# AMP_RF.net
KiCad netlist of a schematic drawn in Altium Designer
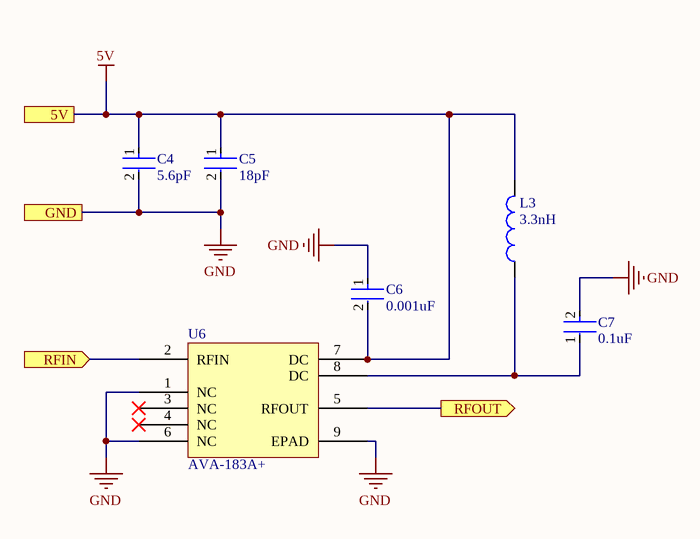
[diagram p0: AMP_RF.SchDoc]

(export (version "E")
  (design (tool "Eeschema 10.0.6"))
  (components
    (comp (ref "C4")
      (value "5.6pF")
      (footprint "FP-0402-L_1_0_1-W_0_5_0_1-MFG")
      (description "General Purpose Ceramic Capacitor, 0402, 5.6pF, 0.25pF, C0G, 30ppm/°C, 50V")
      (fields (field (name "VOLTAGE") "50V"))
      (libsource (lib "Altium Content Vault") (part "b4654b650e69147ec39a6b967a45e02"))
    )
    (comp (ref "C5")
      (value "18pF")
      (footprint "FP-0402-L_1_0_1-W_0_5_0_1-IPC_A")
      (description "General Purpose Ceramic Capacitor, 0402, 18pF, 1%, C0G, 30ppm/°C, 50V")
      (fields (field (name "TOLERANCE") "1%"))
      (libsource (lib "Altium Content Vault") (part "b4654b650e69147ec39a6b967a45e02"))
    )
    (comp (ref "C6")
      (value "0.001uF")
      (footprint "FP-C0402-BB-MFG")
      (description "C0402 1,000 pF C0G 5.00% 25 V")
      (fields (field (name "MANUFACTURER PART NUMBER") "C0402C102J3GACTU"))
      (libsource (lib "Altium Content Vault") (part "b4654b650e69147ec39a6b967a45e02"))
    )
    (comp (ref "C7")
      (value "0.1uF")
      (footprint "FP-GRM15-MFG")
      (description "CAP CER 0.1UF 16V X7R 0402")
      (fields (field (name "MANUFACTURER PART NUMBER") "GRM155R71C104KA88D") (field (name "TOLERANCE") "10%"))
      (libsource (lib "Altium Content Vault") (part "236180d848d6139a670b325ea6854c9"))
    )
    (comp (ref "L3")
      (value "3.3nH")
      (footprint "WE-KI_0805")
      (description "744760033A WE-KI SMT Wire Wound Ceramic Inductor")
      (libsource (lib "Altium Content Vault") (part "Inductor - 1"))
    )
    (comp (ref "U6")
      (value "AVA-183A+")
      (footprint "AVA-183A+ QFN")
      (description "Wideband, Microwave, Monolithic Amplifier, 50Ω, 5 to 18 GHz")
      (libsource (lib "FullyDigital") (part "AVA-183A+"))
    )
  )
  (nets
    (net (code "1") (name "/RFIN") (class "Default")
      (node (ref "U6") (pin "2") (pinfunction "RFIN_2") (pintype "passive"))
    )
    (net (code "2") (name "/RFOUT") (class "Default")
      (node (ref "U6") (pin "5") (pinfunction "RFOUT_5") (pintype "passive"))
    )
    (net (code "3") (name "5V") (class "Default")
      (node (ref "C4") (pin "1") (pinfunction "1_1") (pintype "passive"))
      (node (ref "C5") (pin "1") (pinfunction "1_1") (pintype "passive"))
      (node (ref "C6") (pin "2") (pinfunction "2_2") (pintype "passive"))
      (node (ref "L3") (pin "2") (pinfunction "2_2") (pintype "passive"))
      (node (ref "U6") (pin "7") (pinfunction "DC_7") (pintype "passive"))
    )
    (net (code "4") (name "GND") (class "Default")
      (node (ref "C4") (pin "2") (pinfunction "2_2") (pintype "passive"))
      (node (ref "C5") (pin "2") (pinfunction "2_2") (pintype "passive"))
      (node (ref "C6") (pin "1") (pinfunction "1_1") (pintype "passive"))
      (node (ref "C7") (pin "2") (pinfunction "2_2") (pintype "passive"))
      (node (ref "U6") (pin "1") (pinfunction "NC_1") (pintype "passive"))
      (node (ref "U6") (pin "6") (pinfunction "NC_6") (pintype "passive"))
      (node (ref "U6") (pin "9") (pinfunction "EPAD_9") (pintype "passive"))
    )
    (net (code "5") (name "Net-(C7-Pad1)") (class "Default")
      (node (ref "C7") (pin "1") (pinfunction "1_1") (pintype "passive"))
      (node (ref "L3") (pin "1") (pinfunction "1_1") (pintype "passive"))
      (node (ref "U6") (pin "8") (pinfunction "DC_8") (pintype "passive"))
    )
    (net (code "6") (name "unconnected-(U6-NC-Pad3)") (class "Default")
      (node (ref "U6") (pin "3") (pinfunction "NC_3") (pintype "passive+no_connect"))
    )
    (net (code "7") (name "unconnected-(U6-NC-Pad4)") (class "Default")
      (node (ref "U6") (pin "4") (pinfunction "NC_4") (pintype "passive+no_connect"))
    )
  )
)
